# C64_PSU_Combi.net
KiCad netlist of a schematic drawn in EAGLE
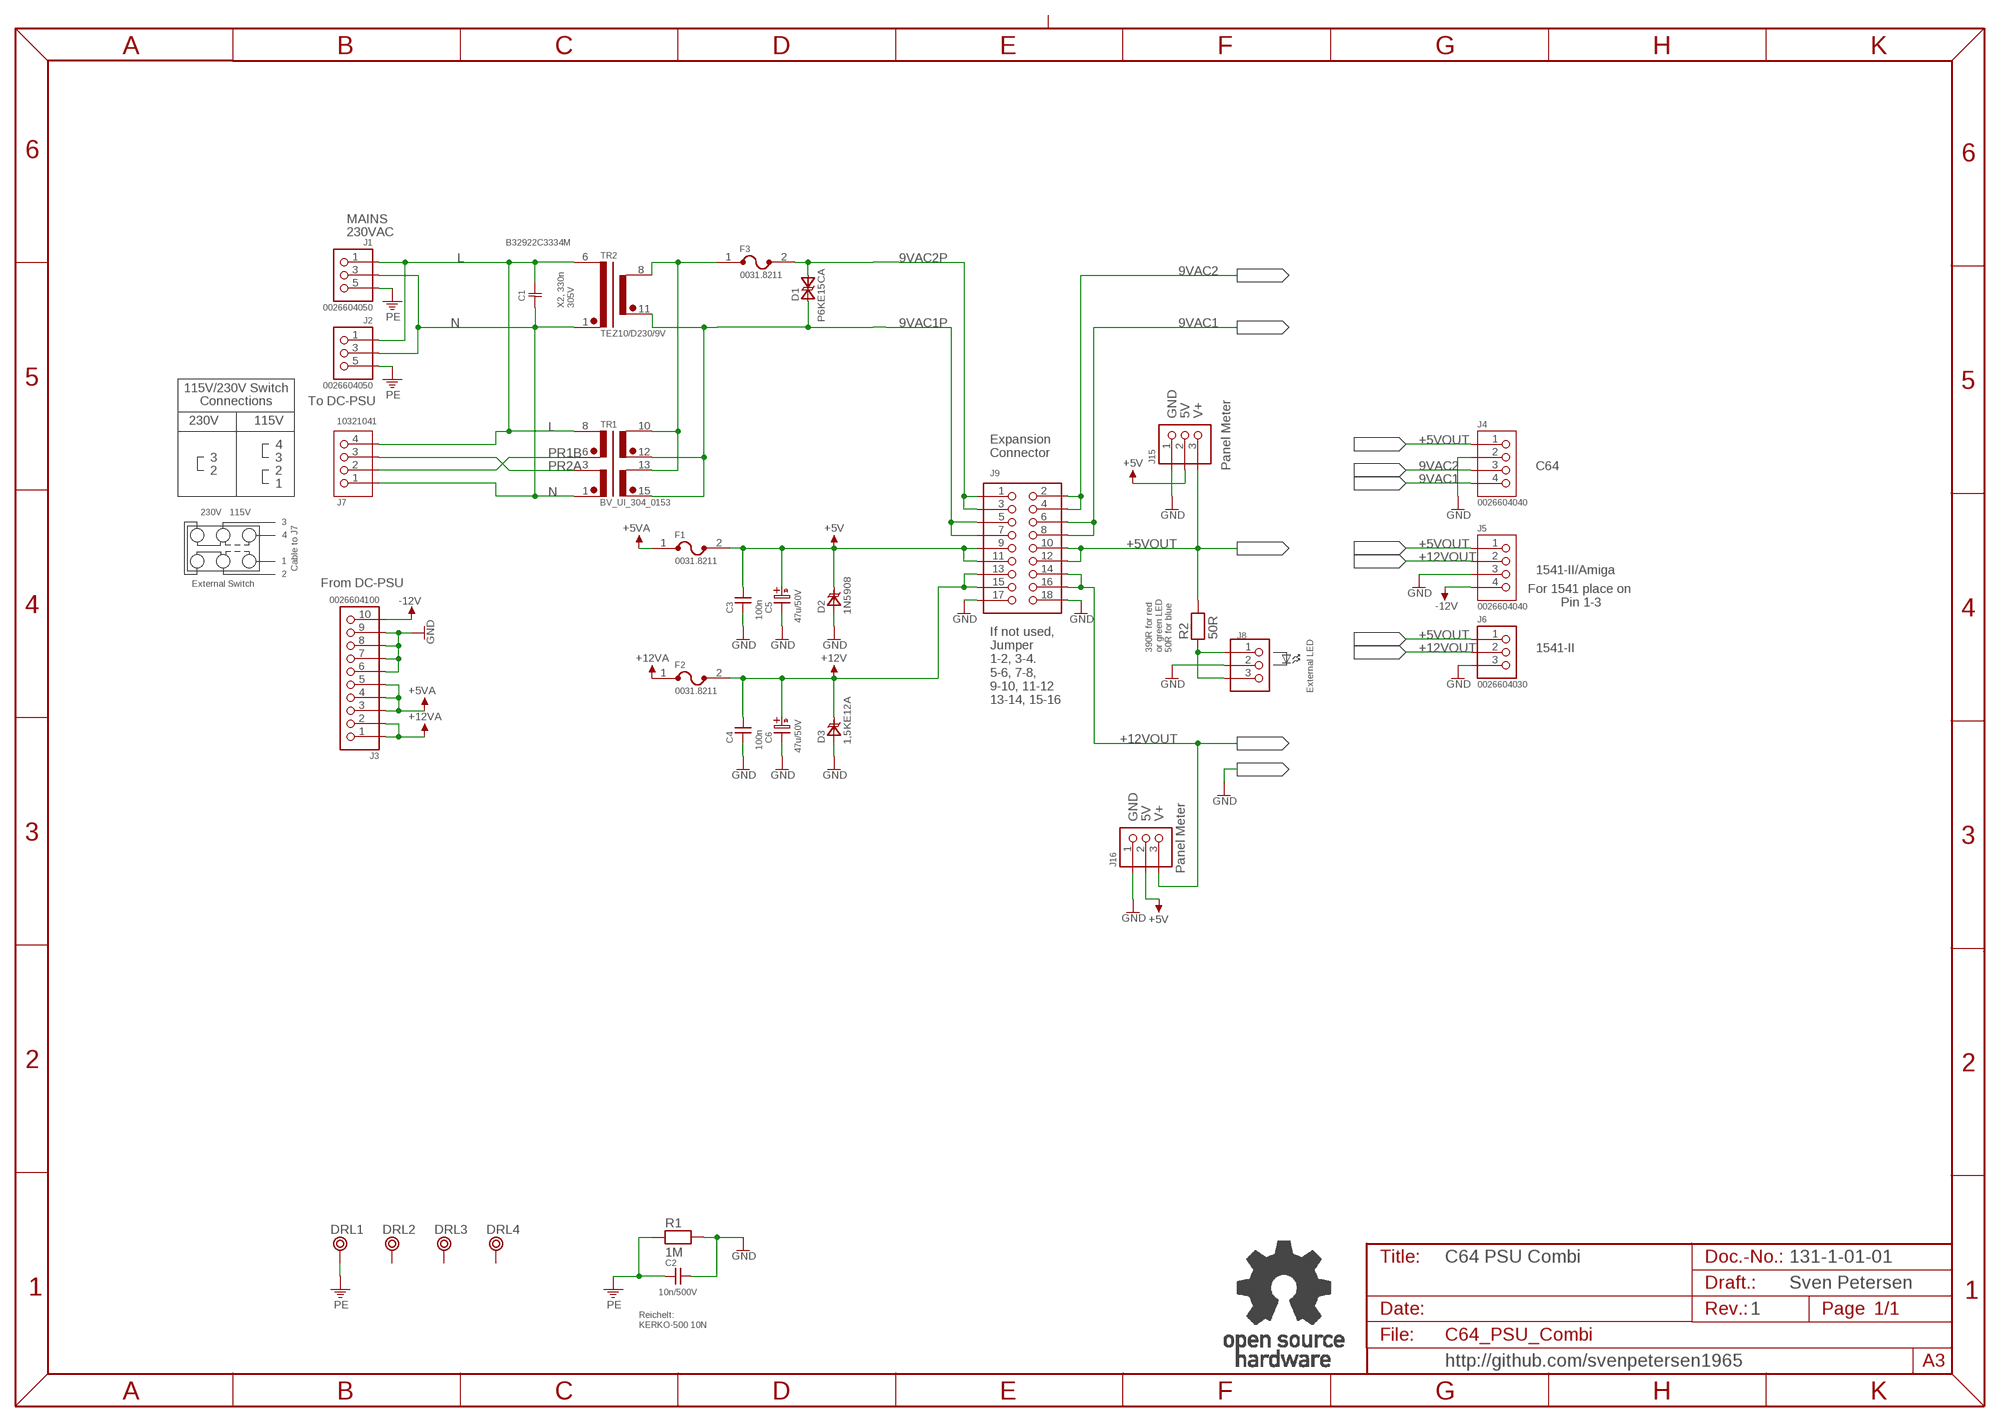
[diagram p0: schematic, sheet 1]

(export (version "E")
  (design (tool "Eeschema 10.0.6"))
  (components
    (comp (ref "C1")
      (value "B32922C3334M")
      (footprint "eagle-import:C-18X8-RM15")
      (libsource (lib "eagle-import") (part "X2--RM15-18X8"))
    )
    (comp (ref "C2")
      (value "10n/500V")
      (footprint "eagle-import:C-5")
      (libsource (lib "eagle-import") (part "CAP02"))
    )
    (comp (ref "C3")
      (value "100n")
      (footprint "eagle-import:C-2,5")
      (libsource (lib "eagle-import") (part "CAP01"))
    )
    (comp (ref "C4")
      (value "100n")
      (footprint "eagle-import:C-2,5")
      (libsource (lib "eagle-import") (part "CAP01"))
    )
    (comp (ref "C5")
      (value "47u/50V")
      (footprint "eagle-import:C07_2,5")
      (libsource (lib "eagle-import") (part "C07/2,5"))
    )
    (comp (ref "C6")
      (value "47u/50V")
      (footprint "eagle-import:C07_2,5")
      (libsource (lib "eagle-import") (part "C07/2,5"))
    )
    (comp (ref "D1")
      (value "P6KE15CA")
      (footprint "eagle-import:CB417NP")
      (libsource (lib "eagle-import") (part "P6KE15CA"))
    )
    (comp (ref "D2")
      (value "1N5908")
      (footprint "eagle-import:CB429")
      (libsource (lib "eagle-import") (part "1N5908"))
    )
    (comp (ref "D3")
      (value "1,5KE12A")
      (footprint "eagle-import:DO-201")
      (libsource (lib "eagle-import") (part "1,5KE12A"))
    )
    (comp (ref "DRL1")
      (value "BOHR3,5OR")
      (footprint "eagle-import:BOHR3,5_OHNE_RESTRICT")
      (libsource (lib "eagle-import") (part "BOHR3,5OR"))
    )
    (comp (ref "DRL2")
      (value "BOHR3,5")
      (footprint "eagle-import:BOHR3,5")
      (libsource (lib "eagle-import") (part "BOHR3,5"))
    )
    (comp (ref "DRL3")
      (value "BOHR3,5")
      (footprint "eagle-import:BOHR3,5")
      (libsource (lib "eagle-import") (part "BOHR3,5"))
    )
    (comp (ref "DRL4")
      (value "BOHR3,5")
      (footprint "eagle-import:BOHR3,5")
      (libsource (lib "eagle-import") (part "BOHR3,5"))
    )
    (comp (ref "F1")
      (value "0031.8211")
      (footprint "eagle-import:0031.8211")
      (libsource (lib "eagle-import") (part "0031.8211"))
    )
    (comp (ref "F2")
      (value "0031.8211")
      (footprint "eagle-import:0031.8211")
      (libsource (lib "eagle-import") (part "0031.8211"))
    )
    (comp (ref "F3")
      (value "0031.8211")
      (footprint "eagle-import:0031.8211")
      (libsource (lib "eagle-import") (part "0031.8211"))
    )
    (comp (ref "J1")
      (value "0026604050")
      (footprint "eagle-import:SPOX_3.96_5P3")
      (libsource (lib "eagle-import") (part "0026604050MOD"))
    )
    (comp (ref "J2")
      (value "0026604050")
      (footprint "eagle-import:SPOX_3.96_5P3")
      (libsource (lib "eagle-import") (part "0026604050MOD"))
    )
    (comp (ref "J3")
      (value "0026604100")
      (footprint "eagle-import:SPOX_3.96_10P")
      (libsource (lib "eagle-import") (part "0026604100"))
    )
    (comp (ref "J4")
      (value "0026604040")
      (footprint "eagle-import:SPOX_3.96_4P")
      (libsource (lib "eagle-import") (part "0026604040"))
    )
    (comp (ref "J5")
      (value "0026604040")
      (footprint "eagle-import:SPOX_3.96_4P")
      (libsource (lib "eagle-import") (part "0026604040"))
    )
    (comp (ref "J6")
      (value "0026604030")
      (footprint "eagle-import:SPOX_3.96_3P")
      (libsource (lib "eagle-import") (part "0026604030"))
    )
    (comp (ref "J7")
      (value "10321041")
      (footprint "eagle-import:SPOX_5.08_4P")
      (libsource (lib "eagle-import") (part "10321041"))
    )
    (comp (ref "J8")
      (value "PINHD-1X3")
      (footprint "eagle-import:1X03")
      (libsource (lib "eagle-import") (part "PINHD-1X3"))
    )
    (comp (ref "J9")
      (value "PINHD-2X9")
      (footprint "eagle-import:2X09")
      (libsource (lib "eagle-import") (part "PINHD-2X9"))
    )
    (comp (ref "J15")
      (value "6410-3P")
      (footprint "eagle-import:6410-3P")
      (libsource (lib "eagle-import") (part "6410-3P"))
    )
    (comp (ref "J16")
      (value "6410-3P")
      (footprint "eagle-import:6410-3P")
      (libsource (lib "eagle-import") (part "6410-3P"))
    )
    (comp (ref "R1")
      (value "1M")
      (footprint "eagle-import:R-10")
      (libsource (lib "eagle-import") (part "RES04"))
    )
    (comp (ref "R2")
      (value "50R")
      (footprint "eagle-import:R-10")
      (libsource (lib "eagle-import") (part "RES04"))
    )
    (comp (ref "TR1")
      (value "BV_UI_304_0153")
      (footprint "eagle-import:UI30")
      (libsource (lib "eagle-import") (part "BV_UI_304_0153"))
    )
    (comp (ref "TR2")
      (value "TEZ10/D230/9V")
      (footprint "eagle-import:TEZ10")
      (libsource (lib "eagle-import") (part "TEZ10/D230/9V"))
    )
    (comp (ref "U$31")
      (value "OPEN_SOURCE_HW")
      (footprint "eagle-import:OPENHW")
      (libsource (lib "eagle-import") (part "OPEN_SOURCE_HW"))
    )
  )
  (nets
    (net (code "1") (name "+5V") (class "Default")
      (node (ref "C3") (pin "2") (pinfunction "2_2") (pintype "passive"))
      (node (ref "C5") (pin "A") (pinfunction "+_A") (pintype "passive"))
      (node (ref "D2") (pin "K") (pinfunction "K_K") (pintype "passive"))
      (node (ref "F1") (pin "2") (pinfunction "2_2") (pintype "passive"))
      (node (ref "J15") (pin "2") (pinfunction "2_2") (pintype "passive"))
      (node (ref "J16") (pin "2") (pinfunction "2_2") (pintype "passive"))
      (node (ref "J9") (pin "11") (pinfunction "11_11") (pintype "passive"))
      (node (ref "J9") (pin "9") (pinfunction "9_9") (pintype "passive"))
    )
    (net (code "2") (name "+5VA") (class "Default")
      (node (ref "F1") (pin "1") (pinfunction "1_1") (pintype "passive"))
      (node (ref "J3") (pin "3") (pinfunction "3_3") (pintype "passive"))
      (node (ref "J3") (pin "4") (pinfunction "4_4") (pintype "passive"))
      (node (ref "J3") (pin "5") (pinfunction "5_5") (pintype "passive"))
    )
    (net (code "3") (name "+12V") (class "Default")
      (node (ref "C4") (pin "2") (pinfunction "2_2") (pintype "passive"))
      (node (ref "C6") (pin "A") (pinfunction "+_A") (pintype "passive"))
      (node (ref "D3") (pin "K") (pinfunction "K_K") (pintype "passive"))
      (node (ref "F2") (pin "2") (pinfunction "2_2") (pintype "passive"))
      (node (ref "J9") (pin "13") (pinfunction "13_13") (pintype "passive"))
      (node (ref "J9") (pin "15") (pinfunction "15_15") (pintype "passive"))
    )
    (net (code "4") (name "+12VA") (class "Default")
      (node (ref "F2") (pin "1") (pinfunction "1_1") (pintype "passive"))
      (node (ref "J3") (pin "1") (pinfunction "1_1") (pintype "passive"))
      (node (ref "J3") (pin "2") (pinfunction "2_2") (pintype "passive"))
    )
    (net (code "5") (name "-12V") (class "Default")
      (node (ref "J3") (pin "10") (pinfunction "10_10") (pintype "passive"))
      (node (ref "J5") (pin "4") (pinfunction "4_4") (pintype "passive"))
    )
    (net (code "6") (name "/+5VOUT") (class "Default")
      (node (ref "J15") (pin "3") (pinfunction "3_3") (pintype "passive"))
      (node (ref "J4") (pin "1") (pinfunction "1_1") (pintype "passive"))
      (node (ref "J5") (pin "1") (pinfunction "1_1") (pintype "passive"))
      (node (ref "J6") (pin "1") (pinfunction "1_1") (pintype "passive"))
      (node (ref "J9") (pin "10") (pinfunction "10_10") (pintype "passive"))
      (node (ref "J9") (pin "12") (pinfunction "12_12") (pintype "passive"))
      (node (ref "R2") (pin "2") (pinfunction "2_2") (pintype "passive"))
    )
    (net (code "7") (name "/+12VOUT") (class "Default")
      (node (ref "J16") (pin "3") (pinfunction "3_3") (pintype "passive"))
      (node (ref "J5") (pin "2") (pinfunction "2_2") (pintype "passive"))
      (node (ref "J6") (pin "2") (pinfunction "2_2") (pintype "passive"))
      (node (ref "J9") (pin "14") (pinfunction "14_14") (pintype "passive"))
      (node (ref "J9") (pin "16") (pinfunction "16_16") (pintype "passive"))
    )
    (net (code "8") (name "/9VAC1") (class "Default")
      (node (ref "J4") (pin "4") (pinfunction "4_4") (pintype "passive"))
      (node (ref "J9") (pin "6") (pinfunction "6_6") (pintype "passive"))
      (node (ref "J9") (pin "8") (pinfunction "8_8") (pintype "passive"))
    )
    (net (code "9") (name "/9VAC1P") (class "Default")
      (node (ref "D1") (pin "A") (pinfunction "A1_A") (pintype "passive"))
      (node (ref "J9") (pin "5") (pinfunction "5_5") (pintype "passive"))
      (node (ref "J9") (pin "7") (pinfunction "7_7") (pintype "passive"))
      (node (ref "TR1") (pin "12") (pinfunction "SEC1B_12") (pintype "passive"))
      (node (ref "TR1") (pin "15") (pinfunction "SEC2B_15") (pintype "passive"))
      (node (ref "TR2") (pin "11") (pinfunction "SEC12_11") (pintype "passive"))
    )
    (net (code "10") (name "/9VAC2") (class "Default")
      (node (ref "J4") (pin "3") (pinfunction "3_3") (pintype "passive"))
      (node (ref "J9") (pin "2") (pinfunction "2_2") (pintype "passive"))
      (node (ref "J9") (pin "4") (pinfunction "4_4") (pintype "passive"))
    )
    (net (code "11") (name "/9VAC2P") (class "Default")
      (node (ref "D1") (pin "K") (pinfunction "A2_K") (pintype "passive"))
      (node (ref "F3") (pin "2") (pinfunction "2_2") (pintype "passive"))
      (node (ref "J9") (pin "1") (pinfunction "1_1") (pintype "passive"))
      (node (ref "J9") (pin "3") (pinfunction "3_3") (pintype "passive"))
    )
    (net (code "12") (name "/L") (class "Default")
      (node (ref "C1") (pin "2") (pinfunction "2_2") (pintype "passive"))
      (node (ref "J1") (pin "1") (pinfunction "1_1") (pintype "passive"))
      (node (ref "J2") (pin "1") (pinfunction "1_1") (pintype "passive"))
      (node (ref "J7") (pin "4") (pinfunction "4_4") (pintype "passive"))
      (node (ref "TR1") (pin "8") (pinfunction "PRI1A_8") (pintype "passive"))
      (node (ref "TR2") (pin "6") (pinfunction "PRI1_6") (pintype "passive"))
    )
    (net (code "13") (name "/N") (class "Default")
      (node (ref "C1") (pin "1") (pinfunction "1_1") (pintype "passive"))
      (node (ref "J1") (pin "3") (pinfunction "2_3") (pintype "passive"))
      (node (ref "J2") (pin "3") (pinfunction "2_3") (pintype "passive"))
      (node (ref "J7") (pin "1") (pinfunction "1_1") (pintype "passive"))
      (node (ref "TR1") (pin "1") (pinfunction "PRI2B_1") (pintype "passive"))
      (node (ref "TR2") (pin "1") (pinfunction "PRI2_1") (pintype "passive"))
    )
    (net (code "14") (name "/PR1B") (class "Default")
      (node (ref "J7") (pin "2") (pinfunction "2_2") (pintype "passive"))
      (node (ref "TR1") (pin "6") (pinfunction "PRI1B_6") (pintype "passive"))
    )
    (net (code "15") (name "/PR2A") (class "Default")
      (node (ref "J7") (pin "3") (pinfunction "3_3") (pintype "passive"))
      (node (ref "TR1") (pin "3") (pinfunction "PRI2A_3") (pintype "passive"))
    )
    (net (code "16") (name "GND") (class "Default")
      (node (ref "C2") (pin "2") (pinfunction "2_2") (pintype "passive"))
      (node (ref "C3") (pin "1") (pinfunction "1_1") (pintype "passive"))
      (node (ref "C4") (pin "1") (pinfunction "1_1") (pintype "passive"))
      (node (ref "C5") (pin "K") (pinfunction "-_K") (pintype "passive"))
      (node (ref "C6") (pin "K") (pinfunction "-_K") (pintype "passive"))
      (node (ref "D2") (pin "A") (pinfunction "A_A") (pintype "passive"))
      (node (ref "D3") (pin "A") (pinfunction "A_A") (pintype "passive"))
      (node (ref "J15") (pin "1") (pinfunction "1_1") (pintype "passive"))
      (node (ref "J16") (pin "1") (pinfunction "1_1") (pintype "passive"))
      (node (ref "J3") (pin "6") (pinfunction "6_6") (pintype "passive"))
      (node (ref "J3") (pin "7") (pinfunction "7_7") (pintype "passive"))
      (node (ref "J3") (pin "8") (pinfunction "8_8") (pintype "passive"))
      (node (ref "J3") (pin "9") (pinfunction "9_9") (pintype "passive"))
      (node (ref "J4") (pin "2") (pinfunction "2_2") (pintype "passive"))
      (node (ref "J5") (pin "3") (pinfunction "3_3") (pintype "passive"))
      (node (ref "J6") (pin "3") (pinfunction "3_3") (pintype "passive"))
      (node (ref "J8") (pin "2") (pinfunction "2_2") (pintype "passive"))
      (node (ref "J9") (pin "17") (pinfunction "17_17") (pintype "passive"))
      (node (ref "J9") (pin "18") (pinfunction "18_18") (pintype "passive"))
      (node (ref "R1") (pin "2") (pinfunction "2_2") (pintype "passive"))
    )
    (net (code "17") (name "Net-(J8-Pad1)") (class "Default")
      (node (ref "J8") (pin "1") (pinfunction "1_1") (pintype "passive"))
      (node (ref "J8") (pin "3") (pinfunction "3_3") (pintype "passive"))
      (node (ref "R2") (pin "1") (pinfunction "1_1") (pintype "passive"))
    )
    (net (code "18") (name "Net-(TR1-SEC1A)") (class "Default")
      (node (ref "F3") (pin "1") (pinfunction "1_1") (pintype "passive"))
      (node (ref "TR1") (pin "10") (pinfunction "SEC1A_10") (pintype "passive"))
      (node (ref "TR1") (pin "13") (pinfunction "SEC2A_13") (pintype "passive"))
      (node (ref "TR2") (pin "8") (pinfunction "SEC11_8") (pintype "passive"))
    )
    (net (code "19") (name "PE") (class "Default")
      (node (ref "C2") (pin "1") (pinfunction "1_1") (pintype "passive"))
      (node (ref "DRL1") (pin "P$1") (pinfunction "P$1_P$1") (pintype "passive"))
      (node (ref "J1") (pin "5") (pinfunction "3_5") (pintype "passive"))
      (node (ref "J2") (pin "5") (pinfunction "3_5") (pintype "passive"))
      (node (ref "R1") (pin "1") (pinfunction "1_1") (pintype "passive"))
    )
    (net (code "20") (name "unconnected-(DRL2-PadP$1)") (class "Default")
      (node (ref "DRL2") (pin "P$1") (pinfunction "P$1_P$1") (pintype "passive"))
    )
    (net (code "21") (name "unconnected-(DRL3-PadP$1)") (class "Default")
      (node (ref "DRL3") (pin "P$1") (pinfunction "P$1_P$1") (pintype "passive"))
    )
    (net (code "22") (name "unconnected-(DRL4-PadP$1)") (class "Default")
      (node (ref "DRL4") (pin "P$1") (pinfunction "P$1_P$1") (pintype "passive"))
    )
  )
)
